# Schematic.net
KiCad netlist of a schematic drawn in EAGLE
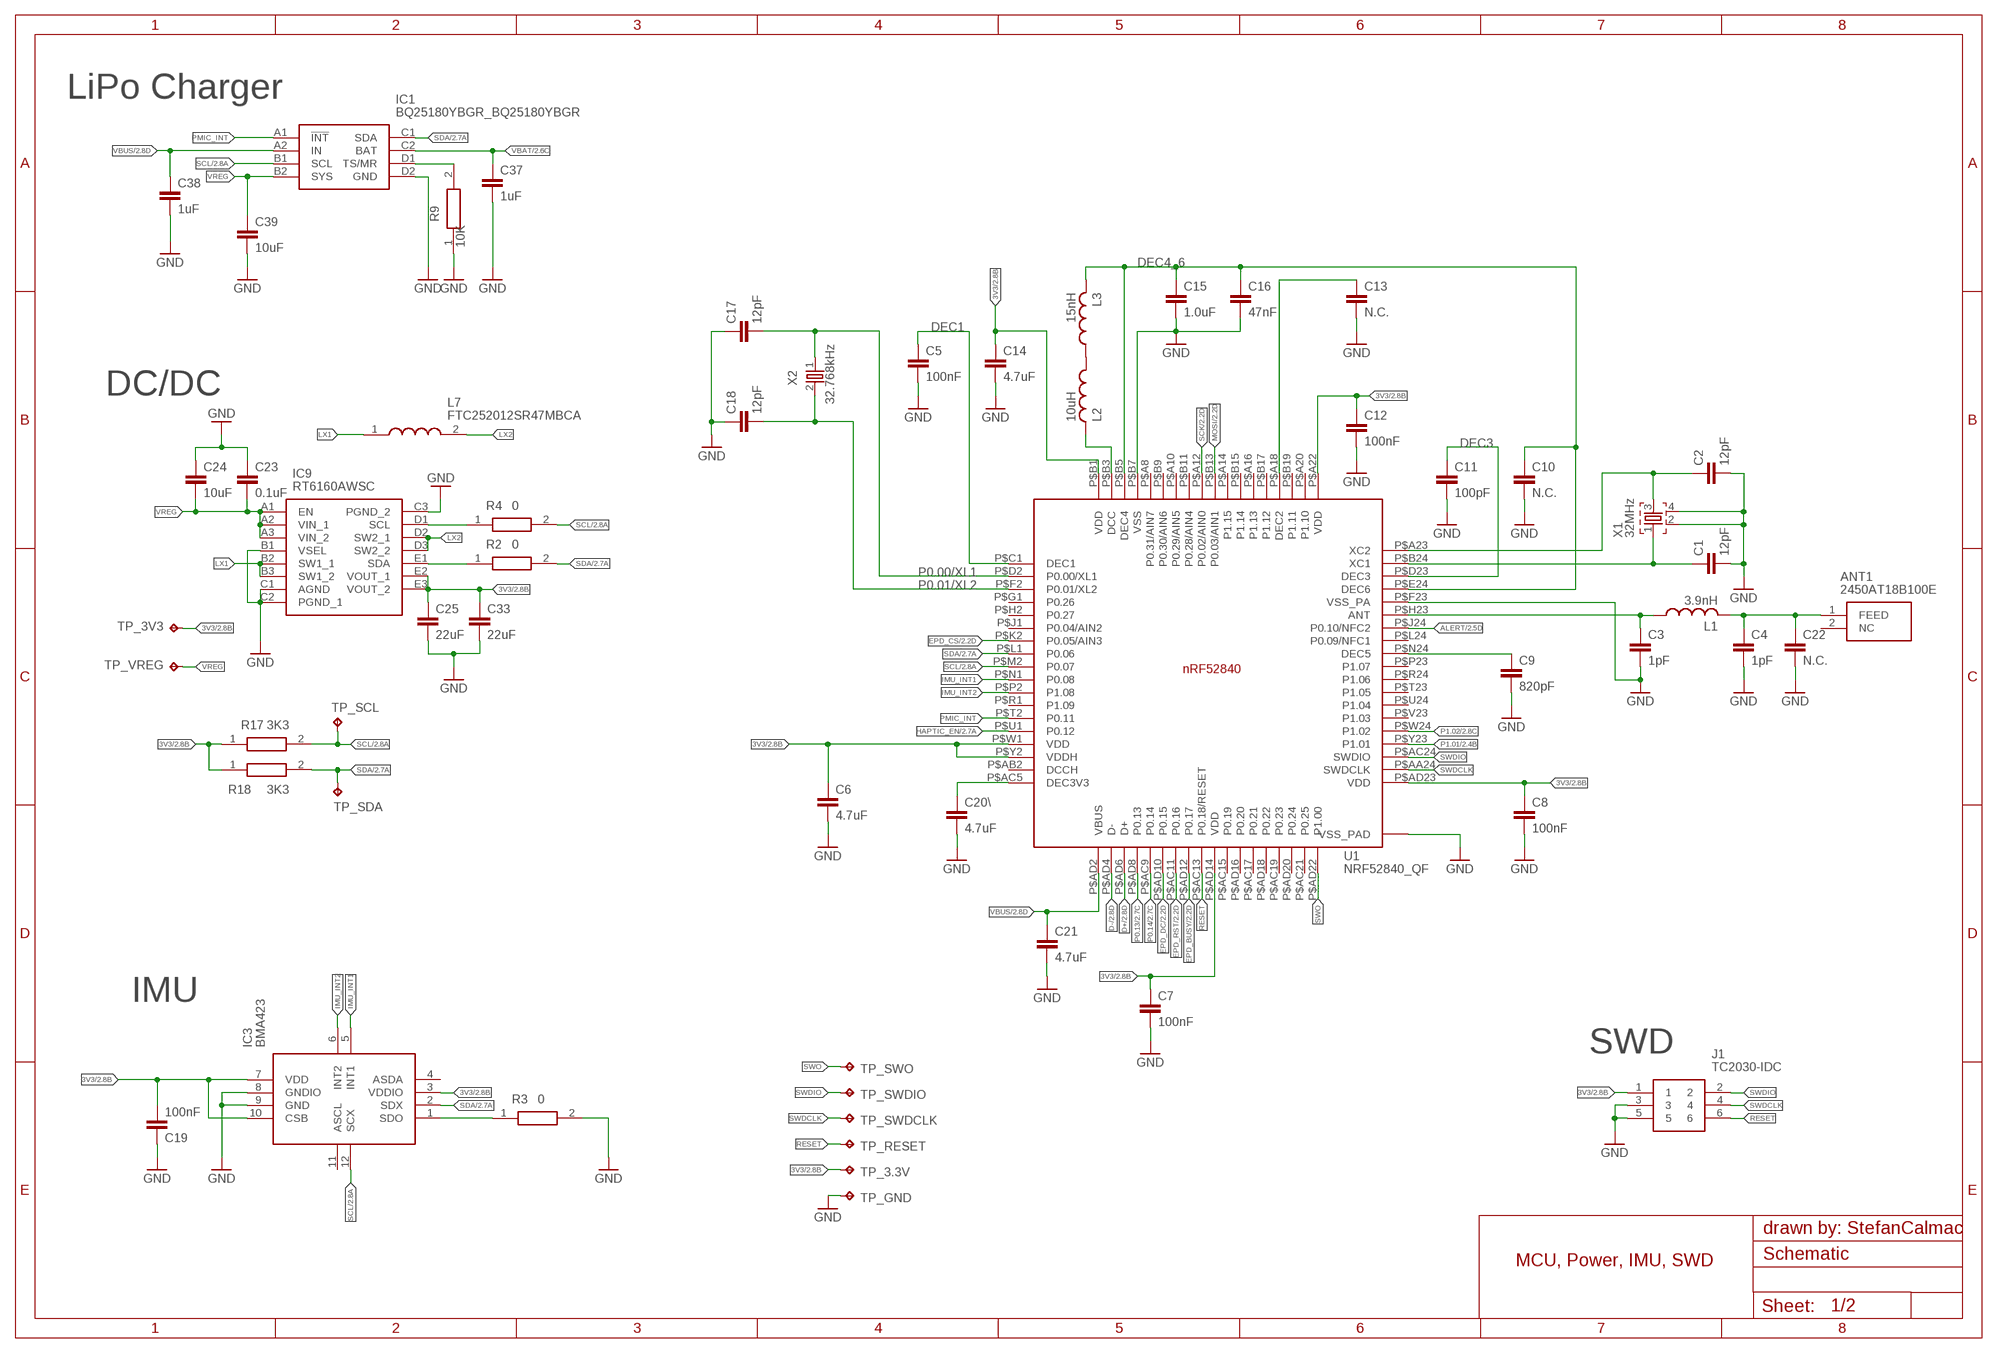
[diagram p0: schematic, sheet 1]
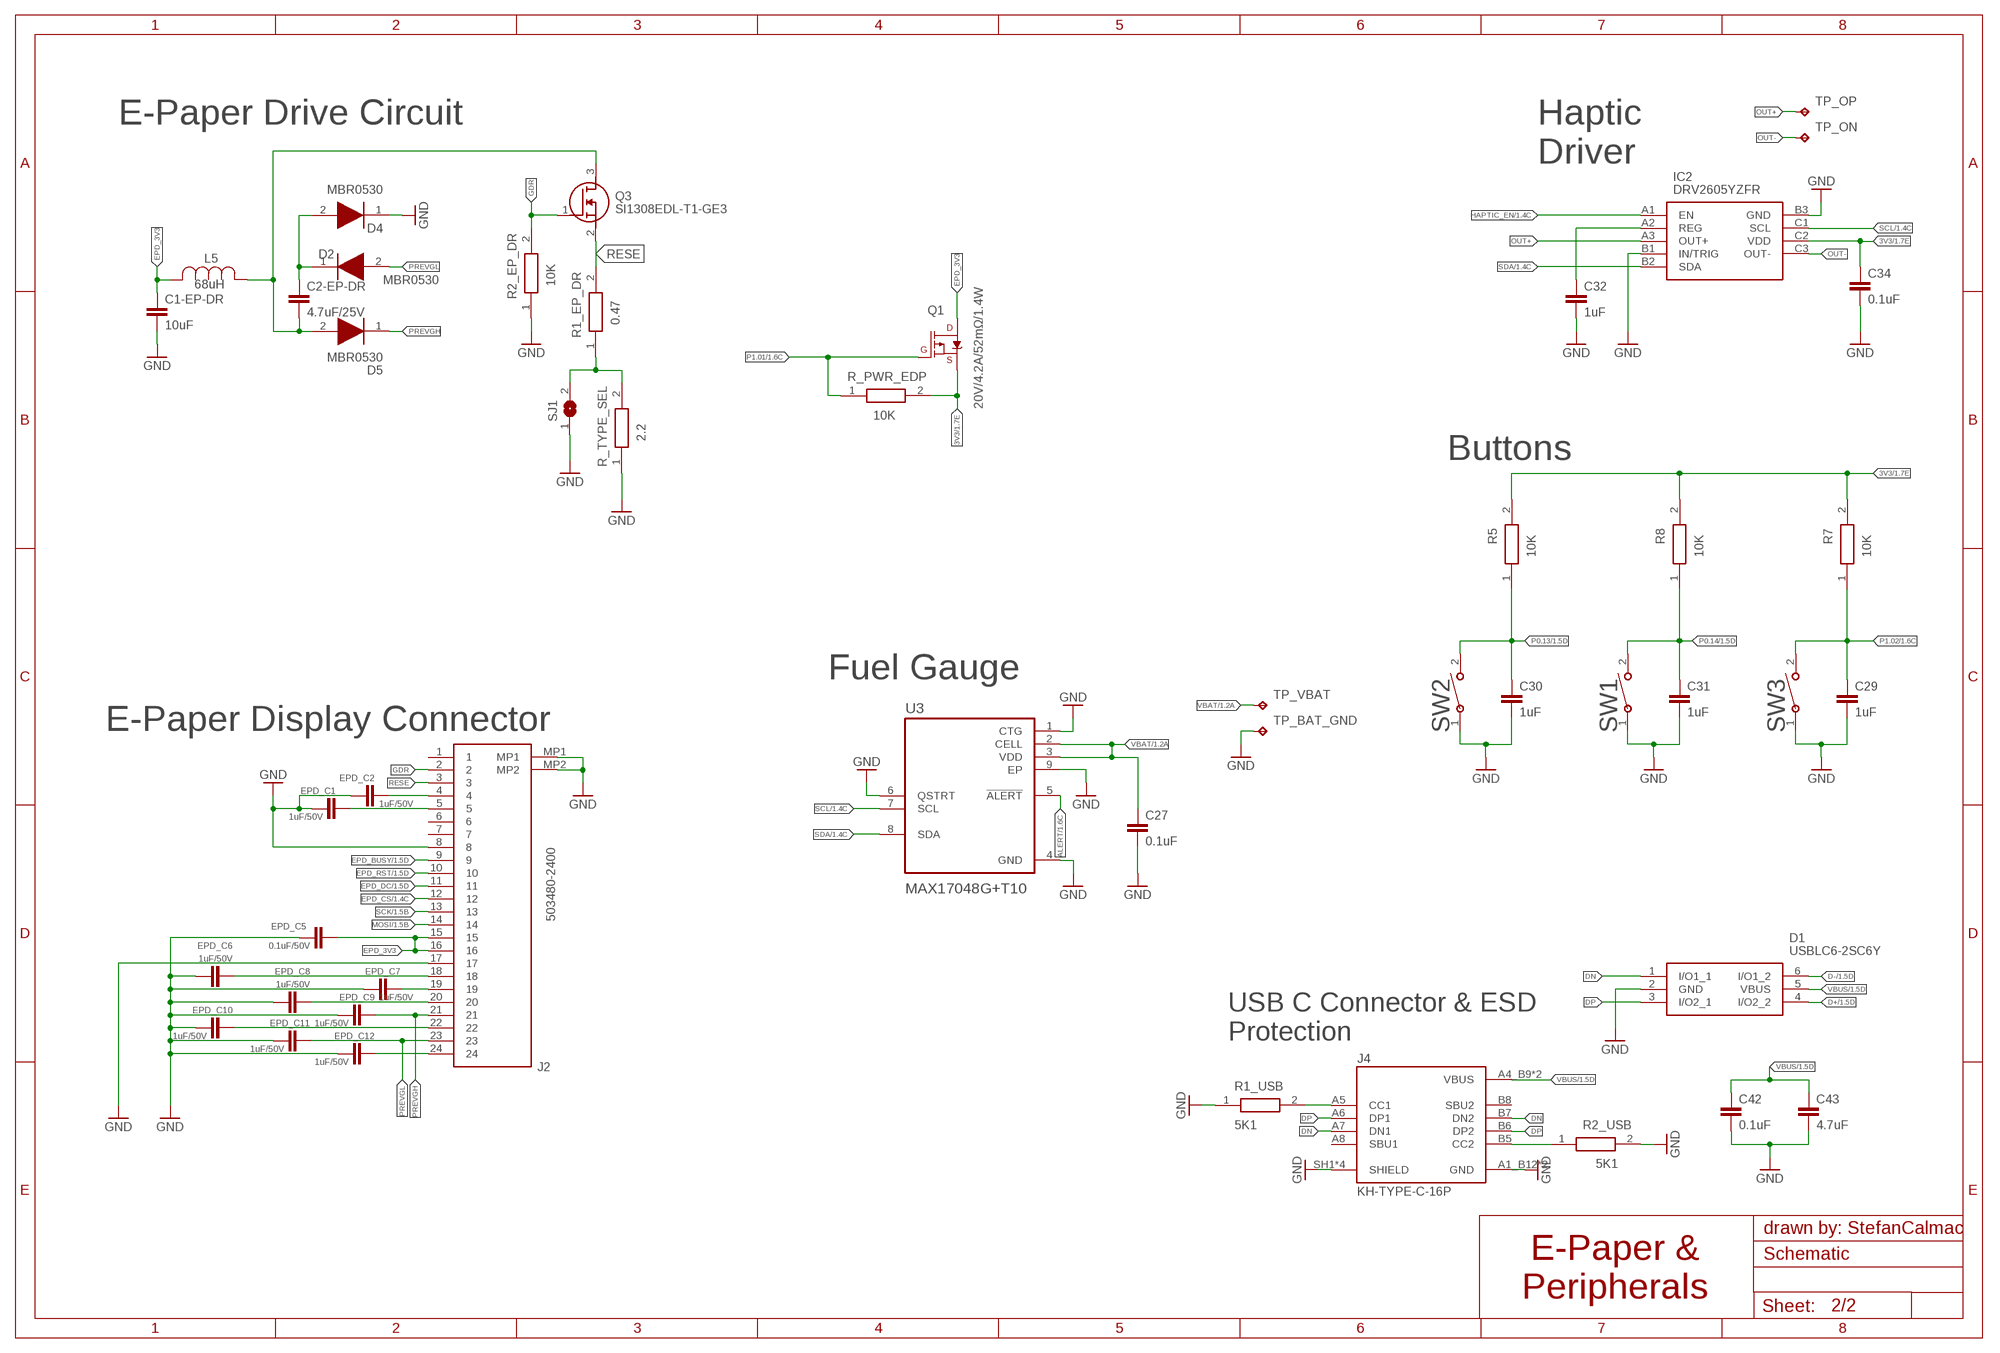
[diagram p1: schematic, sheet 2]

(export (version "E")
  (design (tool "Eeschema 10.0.6"))
  (components
    (comp (ref "ANT1")
      (value "2450AT18B100E")
      (footprint "eagle-import:2450AT18B100E_ANTC3216X140N")
      (fields (field (name "MOUSER_PART_NUMBER") "609-2450AT18B100E"))
      (libsource (lib "eagle-import") (part "2450AT18B100E_2450AT18B100E"))
    )
    (comp (ref "C1")
      (value "12pF")
      (footprint "eagle-import:NORDIC_NRF_3_RESC0201_L")
      (libsource (lib "eagle-import") (part "NORDIC_NRF_3_CAPACITOR_0201_L"))
    )
    (comp (ref "C2")
      (value "12pF")
      (footprint "eagle-import:NORDIC_NRF_3_RESC0201_L")
      (libsource (lib "eagle-import") (part "NORDIC_NRF_3_CAPACITOR_0201_L"))
    )
    (comp (ref "C3")
      (value "1pF")
      (footprint "eagle-import:NORDIC_NRF_3_RESC0201_L")
      (libsource (lib "eagle-import") (part "NORDIC_NRF_3_CAPACITOR_0201_L"))
    )
    (comp (ref "C4")
      (value "1pF")
      (footprint "eagle-import:NORDIC_NRF_3_RESC0201_L")
      (libsource (lib "eagle-import") (part "NORDIC_NRF_3_CAPACITOR_0201_L"))
    )
    (comp (ref "C5")
      (value "100nF")
      (footprint "eagle-import:NORDIC_NRF_3_RESC0201_L")
      (libsource (lib "eagle-import") (part "NORDIC_NRF_3_CAPACITOR_0201_L"))
    )
    (comp (ref "C6")
      (value "4.7uF")
      (footprint "eagle-import:NORDIC_NRF_3_RESC0402_L")
      (libsource (lib "eagle-import") (part "NORDIC_NRF_3_CAPACITOR_0402_L"))
    )
    (comp (ref "C7")
      (value "100nF")
      (footprint "eagle-import:NORDIC_NRF_3_RESC0201_L")
      (libsource (lib "eagle-import") (part "NORDIC_NRF_3_CAPACITOR_0201_L"))
    )
    (comp (ref "C8")
      (value "100nF")
      (footprint "eagle-import:NORDIC_NRF_3_RESC0201_L")
      (libsource (lib "eagle-import") (part "NORDIC_NRF_3_CAPACITOR_0201_L"))
    )
    (comp (ref "C9")
      (value "820pF")
      (footprint "eagle-import:NORDIC_NRF_3_RESC0201_L")
      (libsource (lib "eagle-import") (part "NORDIC_NRF_3_CAPACITOR_0201_L"))
    )
    (comp (ref "C10")
      (value "N.C.")
      (footprint "eagle-import:NORDIC_NRF_3_RESC0201_L")
      (libsource (lib "eagle-import") (part "NORDIC_NRF_3_CAPACITOR_0201_L"))
    )
    (comp (ref "C11")
      (value "100pF")
      (footprint "eagle-import:NORDIC_NRF_3_RESC0201_L")
      (libsource (lib "eagle-import") (part "NORDIC_NRF_3_CAPACITOR_0201_L"))
    )
    (comp (ref "C12")
      (value "100nF")
      (footprint "eagle-import:NORDIC_NRF_3_RESC0201_L")
      (libsource (lib "eagle-import") (part "NORDIC_NRF_3_CAPACITOR_0201_L"))
    )
    (comp (ref "C13")
      (value "N.C.")
      (footprint "eagle-import:NORDIC_NRF_3_RESC0201_L")
      (libsource (lib "eagle-import") (part "NORDIC_NRF_3_CAPACITOR_0201_L"))
    )
    (comp (ref "C14")
      (value "4.7uF")
      (footprint "eagle-import:NORDIC_NRF_3_RESC0402_L")
      (libsource (lib "eagle-import") (part "NORDIC_NRF_3_CAPACITOR_0402_L"))
    )
    (comp (ref "C15")
      (value "1.0uF")
      (footprint "eagle-import:NORDIC_NRF_3_RESC0402_L")
      (libsource (lib "eagle-import") (part "NORDIC_NRF_3_CAPACITOR_0402_L"))
    )
    (comp (ref "C16")
      (value "47nF")
      (footprint "eagle-import:NORDIC_NRF_3_RESC0201_L")
      (libsource (lib "eagle-import") (part "NORDIC_NRF_3_CAPACITOR_0201_L"))
    )
    (comp (ref "C17")
      (value "12pF")
      (footprint "eagle-import:NORDIC_NRF_3_RESC0201_L")
      (libsource (lib "eagle-import") (part "NORDIC_NRF_3_CAPACITOR_0201_L"))
    )
    (comp (ref "C18")
      (value "12pF")
      (footprint "eagle-import:NORDIC_NRF_3_RESC0201_L")
      (libsource (lib "eagle-import") (part "NORDIC_NRF_3_CAPACITOR_0201_L"))
    )
    (comp (ref "C19")
      (value "100nF")
      (footprint "eagle-import:NORDIC_NRF_3_RESC0201_L")
      (libsource (lib "eagle-import") (part "NORDIC_NRF_3_CAPACITOR_0201_L"))
    )
    (comp (ref "C20\\")
      (value "4.7uF")
      (footprint "eagle-import:NORDIC_NRF_3_RESC0402_L")
      (libsource (lib "eagle-import") (part "NORDIC_NRF_3_CAPACITOR_0402_L"))
    )
    (comp (ref "C21")
      (value "4.7uF")
      (footprint "eagle-import:NORDIC_NRF_3_RESC0402_L")
      (libsource (lib "eagle-import") (part "NORDIC_NRF_3_CAPACITOR_0402_L"))
    )
    (comp (ref "C22")
      (value "N.C.")
      (footprint "eagle-import:NORDIC_NRF_3_RESC0201_L")
      (libsource (lib "eagle-import") (part "NORDIC_NRF_3_CAPACITOR_0201_L"))
    )
    (comp (ref "C23")
      (value "0.1uF")
      (footprint "eagle-import:NORDIC_NRF_3_RESC0201_L")
      (libsource (lib "eagle-import") (part "NORDIC_NRF_3_CAPACITOR_0201_L"))
    )
    (comp (ref "C24")
      (value "10uF")
      (footprint "eagle-import:NORDIC_NRF_3_RESC0402_L")
      (libsource (lib "eagle-import") (part "NORDIC_NRF_3_CAPACITOR_0402_L"))
    )
    (comp (ref "C25")
      (value "22uF")
      (footprint "eagle-import:NORDIC_NRF_3_RESC0402_L")
      (libsource (lib "eagle-import") (part "NORDIC_NRF_3_CAPACITOR_0402_L"))
    )
    (comp (ref "C33")
      (value "22uF")
      (footprint "eagle-import:NORDIC_NRF_3_RESC0402_L")
      (libsource (lib "eagle-import") (part "NORDIC_NRF_3_CAPACITOR_0402_L"))
    )
    (comp (ref "C37")
      (value "1uF")
      (footprint "eagle-import:NORDIC_NRF_3_RESC0402_L")
      (libsource (lib "eagle-import") (part "NORDIC_NRF_3_CAPACITOR_0402_L"))
    )
    (comp (ref "C38")
      (value "1uF")
      (footprint "eagle-import:NORDIC_NRF_3_RESC0402_L")
      (libsource (lib "eagle-import") (part "NORDIC_NRF_3_CAPACITOR_0402_L"))
    )
    (comp (ref "C39")
      (value "10uF")
      (footprint "eagle-import:NORDIC_NRF_3_RESC0402_L")
      (libsource (lib "eagle-import") (part "NORDIC_NRF_3_CAPACITOR_0402_L"))
    )
    (comp (ref "IC1")
      (value "BQ25180YBGR_BQ25180YBGR")
      (footprint "eagle-import:BQ25180YBGR_BGA8C40P2X4_100X155X50")
      (fields
        (field (name "ARROW_PART_NUMBER") "BQ25180YBGR")
        (field (name "MOUSER_PART_NUMBER") "595-BQ25180YBGR")
      )
      (libsource (lib "eagle-import") (part "BQ25180YBGR_BQ25180YBGR"))
    )
    (comp (ref "IC3")
      (value "BMA423")
      (footprint "eagle-import:BMA423_BMA423")
      (fields (field (name "MOUSER_PART_NUMBER") "262-BMA423"))
      (libsource (lib "eagle-import") (part "BMA423_BMA423"))
    )
    (comp (ref "IC9")
      (value "RT6160AWSC")
      (footprint "eagle-import:RT6160AWSC_BGA15C40P3X5_140X230X60")
      (fields (field (name "MOUSER_PART_NUMBER") "835-RT6160AWSC"))
      (libsource (lib "eagle-import") (part "RT6160AWSC_RT6160AWSC"))
    )
    (comp (ref "J1")
      (value "TC2030-IDC")
      (footprint "eagle-import:TC2030-IDC_TC2030IDC")
      (libsource (lib "eagle-import") (part "TC2030-IDC_TC2030-IDC"))
    )
    (comp (ref "L1")
      (value "3.9nH")
      (footprint "eagle-import:NORDIC_NRF_2_RESC0402_L")
      (libsource (lib "eagle-import") (part "NORDIC_NRF_2_INDUCTOR_0402_L"))
    )
    (comp (ref "L2")
      (value "10uH")
      (footprint "eagle-import:NORDIC_NRF_2_RESC0603_L")
      (libsource (lib "eagle-import") (part "NORDIC_NRF_2_INDUCTOR_0603_L"))
    )
    (comp (ref "L3")
      (value "15nH")
      (footprint "eagle-import:NORDIC_NRF_2_RESC0402_L")
      (libsource (lib "eagle-import") (part "NORDIC_NRF_2_INDUCTOR_0402_L"))
    )
    (comp (ref "L7")
      (value "FTC252012SR47MBCA")
      (footprint "eagle-import:MLP2016SR47MT0S1_INDC2016X100N")
      (libsource (lib "eagle-import") (part "MLP2016SR47MT0S1_FTC252012SR47MBCA"))
    )
    (comp (ref "R2")
      (value "0")
      (footprint "eagle-import:CPF0201D7K68C1_0201")
      (libsource (lib "eagle-import") (part "CPF0201D7K68C1_CPF0201D7K68C1"))
    )
    (comp (ref "R3")
      (value "0")
      (footprint "eagle-import:CPF0201D7K68C1_0201")
      (libsource (lib "eagle-import") (part "CPF0201D7K68C1_CPF0201D7K68C1"))
    )
    (comp (ref "R4")
      (value "0")
      (footprint "eagle-import:CPF0201D7K68C1_0201")
      (libsource (lib "eagle-import") (part "CPF0201D7K68C1_CPF0201D7K68C1"))
    )
    (comp (ref "R9")
      (value "10K")
      (footprint "eagle-import:CPF0201D7K68C1_0201")
      (libsource (lib "eagle-import") (part "CPF0201D7K68C1_CPF0201D7K68C1"))
    )
    (comp (ref "R17")
      (value "3K3")
      (footprint "eagle-import:CPF0201D7K68C1_0201")
      (libsource (lib "eagle-import") (part "CPF0201D7K68C1_CPF0201D7K68C1"))
    )
    (comp (ref "R18")
      (value "3K3")
      (footprint "eagle-import:CPF0201D7K68C1_0201")
      (libsource (lib "eagle-import") (part "CPF0201D7K68C1_CPF0201D7K68C1"))
    )
    (comp (ref "TP_3.3V")
      (value "HECTOR_WATCH_1_TPTP20R")
      (footprint "eagle-import:HECTOR_WATCH_1_TP20R")
      (libsource (lib "eagle-import") (part "HECTOR_WATCH_1_TPTP20R"))
    )
    (comp (ref "TP_3V3")
      (value "HECTOR_WATCH_1_TPTP20R")
      (footprint "eagle-import:HECTOR_WATCH_1_TP20R")
      (libsource (lib "eagle-import") (part "HECTOR_WATCH_1_TPTP20R"))
    )
    (comp (ref "TP_GND")
      (value "HECTOR_WATCH_1_TPTP20R")
      (footprint "eagle-import:HECTOR_WATCH_1_TP20R")
      (libsource (lib "eagle-import") (part "HECTOR_WATCH_1_TPTP20R"))
    )
    (comp (ref "TP_RESET")
      (value "HECTOR_WATCH_1_TPTP20R")
      (footprint "eagle-import:HECTOR_WATCH_1_TP20R")
      (libsource (lib "eagle-import") (part "HECTOR_WATCH_1_TPTP20R"))
    )
    (comp (ref "TP_SCL")
      (value "HECTOR_WATCH_1_TPTP20R")
      (footprint "eagle-import:HECTOR_WATCH_1_TP20R")
      (libsource (lib "eagle-import") (part "HECTOR_WATCH_1_TPTP20R"))
    )
    (comp (ref "TP_SDA")
      (value "HECTOR_WATCH_1_TPTP20R")
      (footprint "eagle-import:HECTOR_WATCH_1_TP20R")
      (libsource (lib "eagle-import") (part "HECTOR_WATCH_1_TPTP20R"))
    )
    (comp (ref "TP_SWDCLK")
      (value "HECTOR_WATCH_1_TPTP20R")
      (footprint "eagle-import:HECTOR_WATCH_1_TP20R")
      (libsource (lib "eagle-import") (part "HECTOR_WATCH_1_TPTP20R"))
    )
    (comp (ref "TP_SWDIO")
      (value "HECTOR_WATCH_1_TPTP20R")
      (footprint "eagle-import:HECTOR_WATCH_1_TP20R")
      (libsource (lib "eagle-import") (part "HECTOR_WATCH_1_TPTP20R"))
    )
    (comp (ref "TP_SWO")
      (value "HECTOR_WATCH_1_TPTP20R")
      (footprint "eagle-import:HECTOR_WATCH_1_TP20R")
      (libsource (lib "eagle-import") (part "HECTOR_WATCH_1_TPTP20R"))
    )
    (comp (ref "TP_VREG")
      (value "HECTOR_WATCH_1_TPTP20R")
      (footprint "eagle-import:HECTOR_WATCH_1_TP20R")
      (libsource (lib "eagle-import") (part "HECTOR_WATCH_1_TPTP20R"))
    )
    (comp (ref "U1")
      (value "NRF52840_QF")
      (footprint "eagle-import:NORDIC_NRF_4_AQFN50P700X700X85_HS-74N")
      (libsource (lib "eagle-import") (part "NORDIC_NRF_4_NRF52840_QF"))
    )
    (comp (ref "X1")
      (value "32MHz")
      (footprint "eagle-import:NORDIC_NRF_BT-XTAL_2016_N")
      (libsource (lib "eagle-import") (part "NORDIC_NRF_XTAL_32MHZ"))
    )
    (comp (ref "X2")
      (value "32.768kHz")
      (footprint "eagle-import:NORDIC_NRF_1_XTAL_3215_N")
      (libsource (lib "eagle-import") (part "NORDIC_NRF_1_XTAL_32KHZ"))
    )
    (comp (ref "C1-EP-DR")
      (value "10uF")
      (footprint "eagle-import:NORDIC_NRF_3_RESC0402_L")
      (libsource (lib "eagle-import") (part "NORDIC_NRF_3_CAPACITOR_0402_L"))
    )
    (comp (ref "C2-EP-DR")
      (value "4.7uF/25V")
      (footprint "eagle-import:NORDIC_NRF_3_RESC0402_L")
      (libsource (lib "eagle-import") (part "NORDIC_NRF_3_CAPACITOR_0402_L"))
    )
    (comp (ref "C27")
      (value "0.1uF")
      (footprint "eagle-import:NORDIC_NRF_3_RESC0201_L")
      (libsource (lib "eagle-import") (part "NORDIC_NRF_3_CAPACITOR_0201_L"))
    )
    (comp (ref "C29")
      (value "1uF")
      (footprint "eagle-import:NORDIC_NRF_3_RESC0402_L")
      (libsource (lib "eagle-import") (part "NORDIC_NRF_3_CAPACITOR_0402_L"))
    )
    (comp (ref "C30")
      (value "1uF")
      (footprint "eagle-import:NORDIC_NRF_3_RESC0402_L")
      (libsource (lib "eagle-import") (part "NORDIC_NRF_3_CAPACITOR_0402_L"))
    )
    (comp (ref "C31")
      (value "1uF")
      (footprint "eagle-import:NORDIC_NRF_3_RESC0402_L")
      (libsource (lib "eagle-import") (part "NORDIC_NRF_3_CAPACITOR_0402_L"))
    )
    (comp (ref "C32")
      (value "1uF")
      (footprint "eagle-import:NORDIC_NRF_3_RESC0402_L")
      (libsource (lib "eagle-import") (part "NORDIC_NRF_3_CAPACITOR_0402_L"))
    )
    (comp (ref "C34")
      (value "0.1uF")
      (footprint "eagle-import:NORDIC_NRF_3_RESC0201_L")
      (libsource (lib "eagle-import") (part "NORDIC_NRF_3_CAPACITOR_0201_L"))
    )
    (comp (ref "C42")
      (value "0.1uF")
      (footprint "eagle-import:NORDIC_NRF_3_RESC0201_L")
      (libsource (lib "eagle-import") (part "NORDIC_NRF_3_CAPACITOR_0201_L"))
    )
    (comp (ref "C43")
      (value "4.7uF")
      (footprint "eagle-import:NORDIC_NRF_3_RESC0402_L")
      (libsource (lib "eagle-import") (part "NORDIC_NRF_3_CAPACITOR_0402_L"))
    )
    (comp (ref "D1")
      (value "USBLC6-2SC6Y")
      (footprint "eagle-import:SOT95P280X145-6N")
      (fields (field (name "MOUSER_PART_NUMBER") "511-USBLC6-2SC6Y"))
      (libsource (lib "eagle-import") (part "USBLC6-2SC6Y"))
    )
    (comp (ref "D2")
      (value "MBR0530")
      (footprint "eagle-import:ESP32_C6_LIBRARY_5_SOD3716X135N")
      (fields (field (name "MF") "ON Semiconductor"))
      (libsource (lib "eagle-import") (part "ESP32_C6_LIBRARY_5_MBR0530"))
    )
    (comp (ref "D4")
      (value "MBR0530")
      (footprint "eagle-import:ESP32_C6_LIBRARY_5_SOD3716X135N")
      (fields (field (name "MF") "ON Semiconductor"))
      (libsource (lib "eagle-import") (part "ESP32_C6_LIBRARY_5_MBR0530"))
    )
    (comp (ref "D5")
      (value "MBR0530")
      (footprint "eagle-import:ESP32_C6_LIBRARY_5_SOD3716X135N")
      (fields (field (name "MF") "ON Semiconductor"))
      (libsource (lib "eagle-import") (part "ESP32_C6_LIBRARY_5_MBR0530"))
    )
    (comp (ref "EPD_C1")
      (value "1uF/50V")
      (footprint "eagle-import:NORDIC_NRF_3_RESC0402_L")
      (libsource (lib "eagle-import") (part "NORDIC_NRF_3_CAPACITOR_0402_L"))
    )
    (comp (ref "EPD_C2")
      (value "1uF/50V")
      (footprint "eagle-import:NORDIC_NRF_3_RESC0402_L")
      (libsource (lib "eagle-import") (part "NORDIC_NRF_3_CAPACITOR_0402_L"))
    )
    (comp (ref "EPD_C5")
      (value "0.1uF/50V")
      (footprint "eagle-import:NORDIC_NRF_3_RESC0402_L")
      (libsource (lib "eagle-import") (part "NORDIC_NRF_3_CAPACITOR_0402_L"))
    )
    (comp (ref "EPD_C6")
      (value "1uF/50V")
      (footprint "eagle-import:NORDIC_NRF_3_RESC0402_L")
      (libsource (lib "eagle-import") (part "NORDIC_NRF_3_CAPACITOR_0402_L"))
    )
    (comp (ref "EPD_C7")
      (value "1uF/50V")
      (footprint "eagle-import:NORDIC_NRF_3_RESC0402_L")
      (libsource (lib "eagle-import") (part "NORDIC_NRF_3_CAPACITOR_0402_L"))
    )
    (comp (ref "EPD_C8")
      (value "1uF/50V")
      (footprint "eagle-import:NORDIC_NRF_3_RESC0402_L")
      (libsource (lib "eagle-import") (part "NORDIC_NRF_3_CAPACITOR_0402_L"))
    )
    (comp (ref "EPD_C9")
      (value "1uF/50V")
      (footprint "eagle-import:NORDIC_NRF_3_RESC0402_L")
      (libsource (lib "eagle-import") (part "NORDIC_NRF_3_CAPACITOR_0402_L"))
    )
    (comp (ref "EPD_C10")
      (value "1uF/50V")
      (footprint "eagle-import:NORDIC_NRF_3_RESC0402_L")
      (libsource (lib "eagle-import") (part "NORDIC_NRF_3_CAPACITOR_0402_L"))
    )
    (comp (ref "EPD_C11")
      (value "1uF/50V")
      (footprint "eagle-import:NORDIC_NRF_3_RESC0402_L")
      (libsource (lib "eagle-import") (part "NORDIC_NRF_3_CAPACITOR_0402_L"))
    )
    (comp (ref "EPD_C12")
      (value "1uF/50V")
      (footprint "eagle-import:NORDIC_NRF_3_RESC0402_L")
      (libsource (lib "eagle-import") (part "NORDIC_NRF_3_CAPACITOR_0402_L"))
    )
    (comp (ref "IC2")
      (value "DRV2605YZFR")
      (footprint "eagle-import:DRV2605YZFR_BGA9C50P3X3_144X144X62")
      (libsource (lib "eagle-import") (part "DRV2605YZFR_DRV2605YZFR"))
    )
    (comp (ref "J2")
      (value "503480-2400")
      (footprint "eagle-import:503480-2400_5034802400")
      (fields (field (name "MOUSER_PART_NUMBER") "538-503480-2400"))
      (libsource (lib "eagle-import") (part "503480-2400_503480-2400"))
    )
    (comp (ref "J4")
      (value "KH-TYPE-C-16P")
      (footprint "eagle-import:KH-TYPE-C-16P_KINGHELM_KH-TYPE-C-16P")
      (fields (field (name "MF") "kinghelm"))
      (libsource (lib "eagle-import") (part "KH-TYPE-C-16P_KH-TYPE-C-16P"))
    )
    (comp (ref "L5")
      (value "68uH")
      (footprint "eagle-import:ESP32_C6_LIBRARY_2_IND_4828-WE-TPC_WRE")
      (fields
        (field (name "MANUFACTURER_PART_NUMBER") "744043680")
        (field (name "COPYRIGHT") "Copyright (C) 2024 Ultra Librarian. All rights reserved.")
      )
      (libsource (lib "eagle-import") (part "ESP32_C6_LIBRARY_2_744043680IND_4828-WE-TPC_WRE"))
    )
    (comp (ref "Q1")
      (value "20V/4.2A/52mΩ/1.4W")
      (footprint "eagle-import:ESP32_C6_LIBRARY_4_ESP32_C6_LIBRARY_4_ESP32_C6_LIBRARY_4_ESP32_C6_LIBRARY_4_ESP32_WROVER_SPARKFUN-DISCRETESEMI_SOT23-3")
      (libsource (lib "eagle-import") (part "ESP32_C6_LIBRARY_4_ESP32_WROVER_SPARKFUN-DISCRETESEMI_MOSFET_PCH-DMG2305UX-7"))
    )
    (comp (ref "Q3")
      (value "SI1308EDL-T1-GE3")
      (footprint "eagle-import:ESP32_C6_LIBRARY_6_SOT65P210X110-3N")
      (fields (field (name "MF") "Vishay Siliconix"))
      (libsource (lib "eagle-import") (part "ESP32_C6_LIBRARY_6_SI1308EDL-T1-GE3"))
    )
    (comp (ref "R1_EP_DR")
      (value "0.47")
      (footprint "eagle-import:CPF0201D7K68C1_0201")
      (libsource (lib "eagle-import") (part "CPF0201D7K68C1_CPF0201D7K68C1"))
    )
    (comp (ref "R1_USB")
      (value "5K1")
      (footprint "eagle-import:CPF0201D7K68C1_0201")
      (libsource (lib "eagle-import") (part "CPF0201D7K68C1_CPF0201D7K68C1"))
    )
    (comp (ref "R2_EP_DR")
      (value "10K")
      (footprint "eagle-import:CPF0201D7K68C1_0201")
      (libsource (lib "eagle-import") (part "CPF0201D7K68C1_CPF0201D7K68C1"))
    )
    (comp (ref "R2_USB")
      (value "5K1")
      (footprint "eagle-import:CPF0201D7K68C1_0201")
      (libsource (lib "eagle-import") (part "CPF0201D7K68C1_CPF0201D7K68C1"))
    )
    (comp (ref "R5")
      (value "10K")
      (footprint "eagle-import:CPF0201D7K68C1_0201")
      (libsource (lib "eagle-import") (part "CPF0201D7K68C1_CPF0201D7K68C1"))
    )
    (comp (ref "R7")
      (value "10K")
      (footprint "eagle-import:CPF0201D7K68C1_0201")
      (libsource (lib "eagle-import") (part "CPF0201D7K68C1_CPF0201D7K68C1"))
    )
    (comp (ref "R8")
      (value "10K")
      (footprint "eagle-import:CPF0201D7K68C1_0201")
      (libsource (lib "eagle-import") (part "CPF0201D7K68C1_CPF0201D7K68C1"))
    )
    (comp (ref "R_PWR_EDP")
      (value "10K")
      (footprint "eagle-import:CPF0201D7K68C1_0201")
      (libsource (lib "eagle-import") (part "CPF0201D7K68C1_CPF0201D7K68C1"))
    )
    (comp (ref "R_TYPE_SEL")
      (value "2.2")
      (footprint "eagle-import:CPF0201D7K68C1_0201")
      (libsource (lib "eagle-import") (part "CPF0201D7K68C1_CPF0201D7K68C1"))
    )
    (comp (ref "SJ1")
      (value "ESP32_C6_LIBRARY_7_JUMPER_SJ")
      (footprint "eagle-import:ESP32_C6_LIBRARY_7_JUMPER_SJ")
      (libsource (lib "eagle-import") (part "ESP32_C6_LIBRARY_7_JUMPER_SJ"))
    )
    (comp (ref "SW1")
      (value "2025-10-22_07-23-44_LIBRARY_EVP-AKE31ASW_EVP-AKE31A_PAN")
      (footprint "eagle-import:2025-10-22_07-23-44_LIBRARY_SW_EVP-AKE31A_PAN")
      (fields
        (field (name "MANUFACTURER_PART_NUMBER") "EVP-AKE31A")
        (field (name "COPYRIGHT") "Copyright (C) 2025 Ultra Librarian. All rights reserved.")
      )
      (libsource (lib "eagle-import") (part "2025-10-22_07-23-44_LIBRARY_EVP-AKE31ASW_EVP-AKE31A_PAN"))
    )
    (comp (ref "SW2")
      (value "2025-10-22_07-23-44_LIBRARY_EVP-AKE31ASW_EVP-AKE31A_PAN")
      (footprint "eagle-import:2025-10-22_07-23-44_LIBRARY_SW_EVP-AKE31A_PAN")
      (fields
        (field (name "MANUFACTURER_PART_NUMBER") "EVP-AKE31A")
        (field (name "COPYRIGHT") "Copyright (C) 2025 Ultra Librarian. All rights reserved.")
      )
      (libsource (lib "eagle-import") (part "2025-10-22_07-23-44_LIBRARY_EVP-AKE31ASW_EVP-AKE31A_PAN"))
    )
    (comp (ref "SW3")
      (value "2025-10-22_07-23-44_LIBRARY_EVP-AKE31ASW_EVP-AKE31A_PAN")
      (footprint "eagle-import:2025-10-22_07-23-44_LIBRARY_SW_EVP-AKE31A_PAN")
      (fields
        (field (name "MANUFACTURER_PART_NUMBER") "EVP-AKE31A")
        (field (name "COPYRIGHT") "Copyright (C) 2025 Ultra Librarian. All rights reserved.")
      )
      (libsource (lib "eagle-import") (part "2025-10-22_07-23-44_LIBRARY_EVP-AKE31ASW_EVP-AKE31A_PAN"))
    )
    (comp (ref "TP_BAT_GND")
      (value "HECTOR_WATCH_1_TPTP20R")
      (footprint "eagle-import:HECTOR_WATCH_1_TP20R")
      (libsource (lib "eagle-import") (part "HECTOR_WATCH_1_TPTP20R"))
    )
    (comp (ref "TP_ON")
      (value "HECTOR_WATCH_1_TPTP20R")
      (footprint "eagle-import:HECTOR_WATCH_1_TP20R")
      (libsource (lib "eagle-import") (part "HECTOR_WATCH_1_TPTP20R"))
    )
    (comp (ref "TP_OP")
      (value "HECTOR_WATCH_1_TPTP20R")
      (footprint "eagle-import:HECTOR_WATCH_1_TP20R")
      (libsource (lib "eagle-import") (part "HECTOR_WATCH_1_TPTP20R"))
    )
    (comp (ref "TP_VBAT")
      (value "HECTOR_WATCH_1_TPTP20R")
      (footprint "eagle-import:HECTOR_WATCH_1_TP20R")
      (libsource (lib "eagle-import") (part "HECTOR_WATCH_1_TPTP20R"))
    )
    (comp (ref "U3")
      (value "MAX17048G+T10")
      (footprint "eagle-import:ESP32_C6_LIBRARY_SON50P200X200X80-9N")
      (fields (field (name "MF") "Analog Devices"))
      (libsource (lib "eagle-import") (part "ESP32_C6_LIBRARY_MAX17048G+T10"))
    )
  )
  (nets
    (net (code "1") (name "3V3") (class "Default")
      (node (ref "C12") (pin "2") (pinfunction "2_2") (pintype "passive"))
      (node (ref "C14") (pin "1") (pinfunction "1_1") (pintype "passive"))
      (node (ref "C19") (pin "2") (pinfunction "2_2") (pintype "passive"))
      (node (ref "C25") (pin "1") (pinfunction "1_1") (pintype "passive"))
      (node (ref "C33") (pin "1") (pinfunction "1_1") (pintype "passive"))
      (node (ref "C34") (pin "1") (pinfunction "1_1") (pintype "passive"))
      (node (ref "C6") (pin "1") (pinfunction "1_1") (pintype "passive"))
      (node (ref "C7") (pin "2") (pinfunction "2_2") (pintype "passive"))
      (node (ref "C8") (pin "2") (pinfunction "2_2") (pintype "passive"))
      (node (ref "IC2") (pin "C2") (pinfunction "VDD_C2") (pintype "bidirectional"))
      (node (ref "IC3") (pin "10") (pinfunction "CSB_10") (pintype "bidirectional"))
      (node (ref "IC3") (pin "3") (pinfunction "VDDIO_3") (pintype "bidirectional"))
      (node (ref "IC3") (pin "7") (pinfunction "VDD_7") (pintype "bidirectional"))
      (node (ref "IC9") (pin "E2") (pinfunction "VOUT_1_E2") (pintype "bidirectional"))
      (node (ref "IC9") (pin "E3") (pinfunction "VOUT_2_E3") (pintype "bidirectional"))
      (node (ref "J1") (pin "1") (pinfunction "1_1") (pintype "bidirectional"))
      (node (ref "Q1") (pin "2") (pinfunction "S_2") (pintype "bidirectional"))
      (node (ref "R17") (pin "1") (pinfunction "1_1") (pintype "bidirectional"))
      (node (ref "R18") (pin "1") (pinfunction "1_1") (pintype "bidirectional"))
      (node (ref "R5") (pin "2") (pinfunction "2_2") (pintype "bidirectional"))
      (node (ref "R7") (pin "2") (pinfunction "2_2") (pintype "bidirectional"))
      (node (ref "R8") (pin "2") (pinfunction "2_2") (pintype "bidirectional"))
      (node (ref "R_PWR_EDP") (pin "2") (pinfunction "2_2") (pintype "bidirectional"))
      (node (ref "TP_3.3V") (pin "TP") (pinfunction "TP_TP") (pintype "input"))
      (node (ref "TP_3V3") (pin "TP") (pinfunction "TP_TP") (pintype "input"))
      (node (ref "U1") (pin "P$A22") (pinfunction "VDD_P$A22") (pintype "power_in"))
      (node (ref "U1") (pin "P$AD14") (pinfunction "VDD_P$AD14") (pintype "power_in"))
      (node (ref "U1") (pin "P$AD23") (pinfunction "VDD_P$AD23") (pintype "power_in"))
      (node (ref "U1") (pin "P$B1") (pinfunction "VDD_P$B1") (pintype "power_in"))
      (node (ref "U1") (pin "P$W1") (pinfunction "VDD_P$W1") (pintype "power_in"))
      (node (ref "U1") (pin "P$Y2") (pinfunction "VDDH_P$Y2") (pintype "power_in"))
    )
    (net (code "2") (name "ALERT") (class "Default")
      (node (ref "U1") (pin "P$J24") (pinfunction "P0.10/NFC2_P$J24") (pintype "bidirectional"))
      (node (ref "U3") (pin "5") (pinfunction "~{ALERT}_5") (pintype "output"))
    )
    (net (code "3") (name "D+") (class "Default")
      (node (ref "D1") (pin "4") (pinfunction "I/O2_2_4") (pintype "bidirectional"))
      (node (ref "U1") (pin "P$AD6") (pinfunction "D+_P$AD6") (pintype "bidirectional"))
    )
    (net (code "4") (name "D-") (class "Default")
      (node (ref "D1") (pin "6") (pinfunction "I/O1_2_6") (pintype "bidirectional"))
      (node (ref "U1") (pin "P$AD4") (pinfunction "D-_P$AD4") (pintype "bidirectional"))
    )
    (net (code "5") (name "DEC1") (class "Default")
      (node (ref "C5") (pin "2") (pinfunction "2_2") (pintype "passive"))
      (node (ref "U1") (pin "P$C1") (pinfunction "DEC1_P$C1") (pintype "power_in"))
    )
    (net (code "6") (name "DEC3") (class "Default")
      (node (ref "C11") (pin "2") (pinfunction "2_2") (pintype "passive"))
      (node (ref "U1") (pin "P$D23") (pinfunction "DEC3_P$D23") (pintype "bidirectional"))
    )
    (net (code "7") (name "DEC4_6") (class "Default")
      (node (ref "C10") (pin "2") (pinfunction "2_2") (pintype "passive"))
      (node (ref "C15") (pin "1") (pinfunction "1_1") (pintype "passive"))
      (node (ref "C16") (pin "2") (pinfunction "2_2") (pintype "passive"))
      (node (ref "L3") (pin "2") (pinfunction "2_2") (pintype "passive"))
      (node (ref "U1") (pin "P$B5") (pinfunction "DEC4_P$B5") (pintype "power_in"))
      (node (ref "U1") (pin "P$E24") (pinfunction "DEC6_P$E24") (pintype "bidirectional"))
    )
    (net (code "8") (name "DN") (class "Default")
      (node (ref "D1") (pin "1") (pinfunction "I/O1_1_1") (pintype "bidirectional"))
      (node (ref "J4") (pin "A7") (pinfunction "DN1_A7") (pintype "bidirectional"))
      (node (ref "J4") (pin "B7") (pinfunction "DN2_B7") (pintype "bidirectional"))
    )
    (net (code "9") (name "DP") (class "Default")
      (node (ref "D1") (pin "3") (pinfunction "I/O2_1_3") (pintype "bidirectional"))
      (node (ref "J4") (pin "A6") (pinfunction "DP1_A6") (pintype "bidirectional"))
      (node (ref "J4") (pin "B6") (pinfunction "DP2_B6") (pintype "bidirectional"))
    )
    (net (code "10") (name "EPD_3V3") (class "Default")
      (node (ref "C1-EP-DR") (pin "1") (pinfunction "1_1") (pintype "passive"))
      (node (ref "EPD_C5") (pin "2") (pinfunction "2_2") (pintype "passive"))
      (node (ref "J2") (pin "15") (pinfunction "15_15") (pintype "bidirectional"))
      (node (ref "J2") (pin "16") (pinfunction "16_16") (pintype "bidirectional"))
      (node (ref "L5") (pin "2") (pinfunction "2_2") (pintype "passive"))
      (node (ref "Q1") (pin "3") (pinfunction "D_3") (pintype "bidirectional"))
    )
    (net (code "11") (name "EPD_BUSY") (class "Default")
      (node (ref "J2") (pin "9") (pinfunction "9_9") (pintype "bidirectional"))
      (node (ref "U1") (pin "P$AD12") (pinfunction "P0.17_P$AD12") (pintype "bidirectional"))
    )
    (net (code "12") (name "EPD_CS") (class "Default")
      (node (ref "J2") (pin "12") (pinfunction "12_12") (pintype "bidirectional"))
      (node (ref "U1") (pin "P$K2") (pinfunction "P0.05/AIN3_P$K2") (pintype "bidirectional"))
    )
    (net (code "13") (name "EPD_DC") (class "Default")
      (node (ref "J2") (pin "11") (pinfunction "11_11") (pintype "bidirectional"))
      (node (ref "U1") (pin "P$AD10") (pinfunction "P0.15_P$AD10") (pintype "bidirectional"))
    )
    (net (code "14") (name "EPD_RST") (class "Default")
      (node (ref "J2") (pin "10") (pinfunction "10_10") (pintype "bidirectional"))
      (node (ref "U1") (pin "P$AC11") (pinfunction "P0.16_P$AC11") (pintype "bidirectional"))
    )
    (net (code "15") (name "GDR") (class "Default")
      (node (ref "J2") (pin "2") (pinfunction "2_2") (pintype "bidirectional"))
      (node (ref "Q3") (pin "1") (pinfunction "G_1") (pintype "bidirectional"))
      (node (ref "R2_EP_DR") (pin "2") (pinfunction "2_2") (pintype "bidirectional"))
    )
    (net (code "16") (name "GND") (class "Default")
      (node (ref "C1") (pin "1") (pinfunction "1_1") (pintype "passive"))
      (node (ref "C1-EP-DR") (pin "2") (pinfunction "2_2") (pintype "passive"))
      (node (ref "C10") (pin "1") (pinfunction "1_1") (pintype "passive"))
      (node (ref "C11") (pin "1") (pinfunction "1_1") (pintype "passive"))
      (node (ref "C12") (pin "1") (pinfunction "1_1") (pintype "passive"))
      (node (ref "C13") (pin "1") (pinfunction "1_1") (pintype "passive"))
      (node (ref "C14") (pin "2") (pinfunction "2_2") (pintype "passive"))
      (node (ref "C15") (pin "2") (pinfunction "2_2") (pintype "passive"))
      (node (ref "C16") (pin "1") (pinfunction "1_1") (pintype "passive"))
      (node (ref "C17") (pin "1") (pinfunction "1_1") (pintype "passive"))
      (node (ref "C18") (pin "1") (pinfunction "1_1") (pintype "passive"))
      (node (ref "C19") (pin "1") (pinfunction "1_1") (pintype "passive"))
      (node (ref "C2") (pin "2") (pinfunction "2_2") (pintype "passive"))
      (node (ref "C20\\") (pin "2") (pinfunction "2_2") (pintype "passive"))
      (node (ref "C21") (pin "2") (pinfunction "2_2") (pintype "passive"))
      (node (ref "C22") (pin "1") (pinfunction "1_1") (pintype "passive"))
      (node (ref "C23") (pin "1") (pinfunction "1_1") (pintype "passive"))
      (node (ref "C24") (pin "1") (pinfunction "1_1") (pintype "passive"))
      (node (ref "C25") (pin "2") (pinfunction "2_2") (pintype "passive"))
      (node (ref "C27") (pin "2") (pinfunction "2_2") (pintype "passive"))
      (node (ref "C29") (pin "2") (pinfunction "2_2") (pintype "passive"))
      (node (ref "C3") (pin "1") (pinfunction "1_1") (pintype "passive"))
      (node (ref "C30") (pin "2") (pinfunction "2_2") (pintype "passive"))
      (node (ref "C31") (pin "2") (pinfunction "2_2") (pintype "passive"))
      (node (ref "C32") (pin "2") (pinfunction "2_2") (pintype "passive"))
      (node (ref "C33") (pin "2") (pinfunction "2_2") (pintype "passive"))
      (node (ref "C34") (pin "2") (pinfunction "2_2") (pintype "passive"))
      (node (ref "C37") (pin "2") (pinfunction "2_2") (pintype "passive"))
      (node (ref "C38") (pin "2") (pinfunction "2_2") (pintype "passive"))
      (node (ref "C39") (pin "2") (pinfunction "2_2") (pintype "passive"))
      (node (ref "C4") (pin "1") (pinfunction "1_1") (pintype "passive"))
      (node (ref "C42") (pin "2") (pinfunction "2_2") (pintype "passive"))
      (node (ref "C43") (pin "2") (pinfunction "2_2") (pintype "passive"))
      (node (ref "C5") (pin "1") (pinfunction "1_1") (pintype "passive"))
      (node (ref "C6") (pin "2") (pinfunction "2_2") (pintype "passive"))
      (node (ref "C7") (pin "1") (pinfunction "1_1") (pintype "passive"))
      (node (ref "C8") (pin "1") (pinfunction "1_1") (pintype "passive"))
      (node (ref "C9") (pin "1") (pinfunction "1_1") (pintype "passive"))
      (node (ref "D1") (pin "2") (pinfunction "GND_2") (pintype "bidirectional"))
      (node (ref "D4") (pin "1") (pinfunction "K_1") (pintype "bidirectional"))
      (node (ref "EPD_C1") (pin "1") (pinfunction "1_1") (pintype "passive"))
      (node (ref "EPD_C10") (pin "1") (pinfunction "1_1") (pintype "passive"))
      (node (ref "EPD_C11") (pin "1") (pinfunction "1_1") (pintype "passive"))
      (node (ref "EPD_C12") (pin "1") (pinfunction "1_1") (pintype "passive"))
      (node (ref "EPD_C2") (pin "1") (pinfunction "1_1") (pintype "passive"))
      (node (ref "EPD_C5") (pin "1") (pinfunction "1_1") (pintype "passive"))
      (node (ref "EPD_C6") (pin "1") (pinfunction "1_1") (pintype "passive"))
      (node (ref "EPD_C7") (pin "1") (pinfunction "1_1") (pintype "passive"))
      (node (ref "EPD_C8") (pin "1") (pinfunction "1_1") (pintype "passive"))
      (node (ref "EPD_C9") (pin "1") (pinfunction "1_1") (pintype "passive"))
      (node (ref "IC1") (pin "D2") (pinfunction "GND_D2") (pintype "bidirectional"))
      (node (ref "IC2") (pin "B1") (pinfunction "IN/TRIG_B1") (pintype "bidirectional"))
      (node (ref "IC2") (pin "B3") (pinfunction "GND_B3") (pintype "bidirectional"))
      (node (ref "IC3") (pin "8") (pinfunction "GNDIO_8") (pintype "bidirectional"))
      (node (ref "IC3") (pin "9") (pinfunction "GND_9") (pintype "bidirectional"))
      (node (ref "IC9") (pin "B1") (pinfunction "VSEL_B1") (pintype "bidirectional"))
      (node (ref "IC9") (pin "C1") (pinfunction "AGND_C1") (pintype "bidirectional"))
      (node (ref "IC9") (pin "C2") (pinfunction "PGND_1_C2") (pintype "bidirectional"))
      (node (ref "IC9") (pin "C3") (pinfunction "PGND_2_C3") (pintype "bidirectional"))
      (node (ref "J1") (pin "3") (pinfunction "3_3") (pintype "bidirectional"))
      (node (ref "J1") (pin "5") (pinfunction "5_5") (pintype "bidirectional"))
      (node (ref "J2") (pin "17") (pinfunction "17_17") (pintype "bidirectional"))
      (node (ref "J2") (pin "8") (pinfunction "8_8") (pintype "bidirectional"))
      (node (ref "J2") (pin "MP1") (pinfunction "MP1_MP1") (pintype "bidirectional"))
      (node (ref "J2") (pin "MP2") (pinfunction "MP2_MP2") (pintype "bidirectional"))
      (node (ref "J4") (pin "A12_B1") (pinfunction "GND_A12_B1") (pintype "power_in"))
      (node (ref "J4") (pin "A1_B12") (pinfunction "GND_A1_B12") (pintype "power_in"))
      (node (ref "J4") (pin "SH1") (pinfunction "SHIELD_SH1") (pintype "passive"))
      (node (ref "J4") (pin "SH2") (pinfunction "SHIELD_SH2") (pintype "passive"))
      (node (ref "J4") (pin "SH3") (pinfunction "SHIELD_SH3") (pintype "passive"))
      (node (ref "J4") (pin "SH4") (pinfunction "SHIELD_SH4") (pintype "passive"))
      (node (ref "R1_USB") (pin "1") (pinfunction "1_1") (pintype "bidirectional"))
      (node (ref "R2_EP_DR") (pin "1") (pinfunction "1_1") (pintype "bidirectional"))
      (node (ref "R2_USB") (pin "2") (pinfunction "2_2") (pintype "bidirectional"))
      (node (ref "R3") (pin "2") (pinfunction "2_2") (pintype "bidirectional"))
      (node (ref "R9") (pin "1") (pinfunction "1_1") (pintype "bidirectional"))
      (node (ref "R_TYPE_SEL") (pin "1") (pinfunction "1_1") (pintype "bidirectional"))
      (node (ref "SJ1") (pin "1") (pinfunction "1_1") (pintype "passive"))
      (node (ref "SW1") (pin "1") (pinfunction "1_1") (pintype "passive"))
      (node (ref "SW2") (pin "1") (pinfunction "1_1") (pintype "passive"))
      (node (ref "SW3") (pin "1") (pinfunction "1_1") (pintype "passive"))
      (node (ref "TP_BAT_GND") (pin "TP") (pinfunction "TP_TP") (pintype "input"))
      (node (ref "TP_GND") (pin "TP") (pinfunction "TP_TP") (pintype "input"))
      (node (ref "U1") (pin "P$74") (pinfunction "VSS_PAD_P$74") (pintype "bidirectional"))
      (node (ref "U1") (pin "P$75") (pinfunction "VSS_PAD_P$75") (pintype "bidirectional"))
      (node (ref "U1") (pin "P$76") (pinfunction "VSS_PAD_P$76") (pintype "bidirectional"))
      (node (ref "U1") (pin "P$77") (pinfunction "VSS_PAD_P$77") (pintype "bidirectional"))
      (node (ref "U1") (pin "P$78") (pinfunction "VSS_PAD_P$78") (pintype "bidirectional"))
      (node (ref "U1") (pin "P$79") (pinfunction "VSS_PAD_P$79") (pintype "bidirectional"))
      (node (ref "U1") (pin "P$80") (pinfunction "VSS_PAD_P$80") (pintype "bidirectional"))
      (node (ref "U1") (pin "P$81") (pinfunction "VSS_PAD_P$81") (pintype "bidirectional"))
      (node (ref "U1") (pin "P$82") (pinfunction "VSS_PAD_P$82") (pintype "bidirectional"))
      (node (ref "U1") (pin "P$83") (pinfunction "VSS_PAD_P$83") (pintype "bidirectional"))
      (node (ref "U1") (pin "P$84") (pinfunction "VSS_PAD_P$84") (pintype "bidirectional"))
      (node (ref "U1") (pin "P$85") (pinfunction "VSS_PAD_P$85") (pintype "bidirectional"))
      (node (ref "U1") (pin "P$86") (pinfunction "VSS_PAD_P$86") (pintype "bidirectional"))
      (node (ref "U1") (pin "P$87") (pinfunction "VSS_PAD_P$87") (pintype "bidirectional"))
      (node (ref "U1") (pin "P$88") (pinfunction "VSS_PAD_P$88") (pintype "bidirectional"))
      (node (ref "U1") (pin "P$89") (pinfunction "VSS_PAD_P$89") (pintype "bidirectional"))
      (node (ref "U1") (pin "P$90") (pinfunction "VSS_PAD_P$90") (pintype "bidirectional"))
      (node (ref "U1") (pin "P$B7") (pinfunction "VSS_P$B7") (pintype "power_in"))
      (node (ref "U1") (pin "P$F23") (pinfunction "VSS_PA_P$F23") (pintype "bidirectional"))
      (node (ref "U3") (pin "1") (pinfunction "CTG_1") (pintype "power_in"))
      (node (ref "U3") (pin "4") (pinfunction "GND_4") (pintype "power_in"))
      (node (ref "U3") (pin "6") (pinfunction "QSTRT_6") (pintype "input"))
      (node (ref "U3") (pin "9") (pinfunction "EP_9") (pintype "power_in"))
      (node (ref "X1") (pin "2") (pinfunction "2_2") (pintype "passive"))
      (node (ref "X1") (pin "4") (pinfunction "4_4") (pintype "passive"))
    )
    (net (code "17") (name "HAPTIC_EN") (class "Default")
      (node (ref "IC2") (pin "A1") (pinfunction "EN_A1") (pintype "bidirectional"))
      (node (ref "U1") (pin "P$U1") (pinfunction "P0.12_P$U1") (pintype "bidirectional"))
    )
    (net (code "18") (name "IMU_INT1") (class "Default")
      (node (ref "IC3") (pin "5") (pinfunction "INT1_5") (pintype "bidirectional"))
      (node (ref "U1") (pin "P$N1") (pinfunction "P0.08_P$N1") (pintype "bidirectional"))
    )
    (net (code "19") (name "IMU_INT2") (class "Default")
      (node (ref "IC3") (pin "6") (pinfunction "INT2_6") (pintype "bidirectional"))
      (node (ref "U1") (pin "P$P2") (pinfunction "P1.08_P$P2") (pintype "bidirectional"))
    )
    (net (code "20") (name "LX1") (class "Default")
      (node (ref "IC9") (pin "B2") (pinfunction "SW1_1_B2") (pintype "bidirectional"))
      (node (ref "IC9") (pin "B3") (pinfunction "SW1_2_B3") (pintype "bidirectional"))
      (node (ref "L7") (pin "1") (pinfunction "1_1") (pintype "bidirectional"))
    )
    (net (code "21") (name "LX2") (class "Default")
      (node (ref "IC9") (pin "D2") (pinfunction "SW2_1_D2") (pintype "bidirectional"))
      (node (ref "IC9") (pin "D3") (pinfunction "SW2_2_D3") (pintype "bidirectional"))
      (node (ref "L7") (pin "2") (pinfunction "2_2") (pintype "bidirectional"))
    )
    (net (code "22") (name "MOSI") (class "Default")
      (node (ref "J2") (pin "14") (pinfunction "14_14") (pintype "bidirectional"))
      (node (ref "U1") (pin "P$B13") (pinfunction "P0.03/AIN1_P$B13") (pintype "bidirectional"))
    )
    (net (code "23") (name "Net-(ANT1-FEED)") (class "Default")
      (node (ref "ANT1") (pin "1") (pinfunction "FEED_1") (pintype "input"))
      (node (ref "C22") (pin "2") (pinfunction "2_2") (pintype "passive"))
      (node (ref "C4") (pin "2") (pinfunction "2_2") (pintype "passive"))
      (node (ref "L1") (pin "2") (pinfunction "2_2") (pintype "passive"))
    )
    (net (code "24") (name "Net-(D2-K)") (class "Default")
      (node (ref "C2-EP-DR") (pin "1") (pinfunction "1_1") (pintype "passive"))
      (node (ref "D2") (pin "1") (pinfunction "K_1") (pintype "bidirectional"))
      (node (ref "D4") (pin "2") (pinfunction "A_2") (pintype "bidirectional"))
    )
    (net (code "25") (name "Net-(D5-A)") (class "Default")
      (node (ref "C2-EP-DR") (pin "2") (pinfunction "2_2") (pintype "passive"))
      (node (ref "D5") (pin "2") (pinfunction "A_2") (pintype "bidirectional"))
      (node (ref "L5") (pin "1") (pinfunction "1_1") (pintype "passive"))
      (node (ref "Q3") (pin "3") (pinfunction "D_3") (pintype "bidirectional"))
    )
    (net (code "26") (name "Net-(EPD_C1-Pad2)") (class "Default")
      (node (ref "EPD_C1") (pin "2") (pinfunction "2_2") (pintype "passive"))
      (node (ref "J2") (pin "5") (pinfunction "5_5") (pintype "bidirectional"))
    )
    (net (code "27") (name "Net-(EPD_C2-Pad2)") (class "Default")
      (node (ref "EPD_C2") (pin "2") (pinfunction "2_2") (pintype "passive"))
      (node (ref "J2") (pin "4") (pinfunction "4_4") (pintype "bidirectional"))
    )
    (net (code "28") (name "Net-(EPD_C6-Pad2)") (class "Default")
      (node (ref "EPD_C6") (pin "2") (pinfunction "2_2") (pintype "passive"))
      (node (ref "J2") (pin "18") (pinfunction "18_18") (pintype "bidirectional"))
    )
    (net (code "29") (name "Net-(EPD_C7-Pad2)") (class "Default")
      (node (ref "EPD_C7") (pin "2") (pinfunction "2_2") (pintype "passive"))
      (node (ref "J2") (pin "19") (pinfunction "19_19") (pintype "bidirectional"))
    )
    (net (code "30") (name "Net-(EPD_C8-Pad2)") (class "Default")
      (node (ref "EPD_C8") (pin "2") (pinfunction "2_2") (pintype "passive"))
      (node (ref "J2") (pin "20") (pinfunction "20_20") (pintype "bidirectional"))
    )
    (net (code "31") (name "Net-(EPD_C10-Pad2)") (class "Default")
      (node (ref "EPD_C10") (pin "2") (pinfunction "2_2") (pintype "passive"))
      (node (ref "J2") (pin "22") (pinfunction "22_22") (pintype "bidirectional"))
    )
    (net (code "32") (name "Net-(EPD_C12-Pad2)") (class "Default")
      (node (ref "EPD_C12") (pin "2") (pinfunction "2_2") (pintype "passive"))
      (node (ref "J2") (pin "24") (pinfunction "24_24") (pintype "bidirectional"))
    )
    (net (code "33") (name "Net-(IC1-TS{slash}MR)") (class "Default")
      (node (ref "IC1") (pin "D1") (pinfunction "TS/MR_D1") (pintype "bidirectional"))
      (node (ref "R9") (pin "2") (pinfunction "2_2") (pintype "bidirectional"))
    )
    (net (code "34") (name "Net-(IC2-REG)") (class "Default")
      (node (ref "C32") (pin "1") (pinfunction "1_1") (pintype "passive"))
      (node (ref "IC2") (pin "A2") (pinfunction "REG_A2") (pintype "bidirectional"))
    )
    (net (code "35") (name "Net-(IC3-SDO)") (class "Default")
      (node (ref "IC3") (pin "1") (pinfunction "SDO_1") (pintype "bidirectional"))
      (node (ref "R3") (pin "1") (pinfunction "1_1") (pintype "bidirectional"))
    )
    (net (code "36") (name "Net-(IC9-SCL)") (class "Default")
      (node (ref "IC9") (pin "D1") (pinfunction "SCL_D1") (pintype "bidirectional"))
      (node (ref "R4") (pin "1") (pinfunction "1_1") (pintype "bidirectional"))
    )
    (net (code "37") (name "Net-(IC9-SDA)") (class "Default")
      (node (ref "IC9") (pin "E1") (pinfunction "SDA_E1") (pintype "bidirectional"))
      (node (ref "R2") (pin "1") (pinfunction "1_1") (pintype "bidirectional"))
    )
    (net (code "38") (name "Net-(J4-CC1)") (class "Default")
      (node (ref "J4") (pin "A5") (pinfunction "CC1_A5") (pintype "bidirectional"))
      (node (ref "R1_USB") (pin "2") (pinfunction "2_2") (pintype "bidirectional"))
    )
    (net (code "39") (name "Net-(J4-CC2)") (class "Default")
      (node (ref "J4") (pin "B5") (pinfunction "CC2_B5") (pintype "bidirectional"))
      (node (ref "R2_USB") (pin "1") (pinfunction "1_1") (pintype "bidirectional"))
    )
    (net (code "40") (name "Net-(L2-Pad1)") (class "Default")
      (node (ref "L2") (pin "1") (pinfunction "1_1") (pintype "passive"))
      (node (ref "L3") (pin "1") (pinfunction "1_1") (pintype "passive"))
    )
    (net (code "41") (name "Net-(R1_EP_DR-Pad1)") (class "Default")
      (node (ref "R1_EP_DR") (pin "1") (pinfunction "1_1") (pintype "bidirectional"))
      (node (ref "R_TYPE_SEL") (pin "2") (pinfunction "2_2") (pintype "bidirectional"))
      (node (ref "SJ1") (pin "2") (pinfunction "2_2") (pintype "passive"))
    )
    (net (code "42") (name "Net-(U1-ANT)") (class "Default")
      (node (ref "C3") (pin "2") (pinfunction "2_2") (pintype "passive"))
      (node (ref "L1") (pin "1") (pinfunction "1_1") (pintype "passive"))
      (node (ref "U1") (pin "P$H23") (pinfunction "ANT_P$H23") (pintype "bidirectional"))
    )
    (net (code "43") (name "Net-(U1-DCC)") (class "Default")
      (node (ref "L2") (pin "2") (pinfunction "2_2") (pintype "passive"))
      (node (ref "U1") (pin "P$B3") (pinfunction "DCC_P$B3") (pintype "output"))
    )
    (net (code "44") (name "Net-(U1-DEC2)") (class "Default")
      (node (ref "C13") (pin "2") (pinfunction "2_2") (pintype "passive"))
      (node (ref "U1") (pin "P$A18") (pinfunction "DEC2_P$A18") (pintype "bidirectional"))
    )
    (net (code "45") (name "Net-(U1-DEC3V3)") (class "Default")
      (node (ref "C20\\") (pin "1") (pinfunction "1_1") (pintype "passive"))
      (node (ref "U1") (pin "P$AC5") (pinfunction "DEC3V3_P$AC5") (pintype "bidirectional"))
    )
    (net (code "46") (name "Net-(U1-DEC5)") (class "Default")
      (node (ref "C9") (pin "2") (pinfunction "2_2") (pintype "passive"))
      (node (ref "U1") (pin "P$N24") (pinfunction "DEC5_P$N24") (pintype "bidirectional"))
    )
    (net (code "47") (name "Net-(U1-XC1)") (class "Default")
      (node (ref "C1") (pin "2") (pinfunction "2_2") (pintype "passive"))
      (node (ref "U1") (pin "P$B24") (pinfunction "XC1_P$B24") (pintype "input"))
      (node (ref "X1") (pin "1") (pinfunction "1_1") (pintype "passive"))
    )
    (net (code "48") (name "Net-(U1-XC2)") (class "Default")
      (node (ref "C2") (pin "1") (pinfunction "1_1") (pintype "passive"))
      (node (ref "U1") (pin "P$A23") (pinfunction "XC2_P$A23") (pintype "output"))
      (node (ref "X1") (pin "3") (pinfunction "3_3") (pintype "passive"))
    )
    (net (code "49") (name "OUT+") (class "Default")
      (node (ref "IC2") (pin "A3") (pinfunction "OUT+_A3") (pintype "bidirectional"))
      (node (ref "TP_OP") (pin "TP") (pinfunction "TP_TP") (pintype "input"))
    )
    (net (code "50") (name "OUT-") (class "Default")
      (node (ref "IC2") (pin "C3") (pinfunction "OUT-_C3") (pintype "bidirectional"))
      (node (ref "TP_ON") (pin "TP") (pinfunction "TP_TP") (pintype "input"))
    )
    (net (code "51") (name "P0.00{slash}XL1") (class "Default")
      (node (ref "C17") (pin "2") (pinfunction "2_2") (pintype "passive"))
      (node (ref "U1") (pin "P$D2") (pinfunction "P0.00/XL1_P$D2") (pintype "bidirectional"))
      (node (ref "X2") (pin "1") (pinfunction "1_1") (pintype "passive"))
    )
    (net (code "52") (name "P0.01{slash}XL2") (class "Default")
      (node (ref "C18") (pin "2") (pinfunction "2_2") (pintype "passive"))
      (node (ref "U1") (pin "P$F2") (pinfunction "P0.01/XL2_P$F2") (pintype "bidirectional"))
      (node (ref "X2") (pin "2") (pinfunction "2_2") (pintype "passive"))
    )
    (net (code "53") (name "P0.13") (class "Default")
      (node (ref "C30") (pin "1") (pinfunction "1_1") (pintype "passive"))
      (node (ref "R5") (pin "1") (pinfunction "1_1") (pintype "bidirectional"))
      (node (ref "SW2") (pin "2") (pinfunction "2_2") (pintype "passive"))
      (node (ref "U1") (pin "P$AD8") (pinfunction "P0.13_P$AD8") (pintype "bidirectional"))
    )
    (net (code "54") (name "P0.14") (class "Default")
      (node (ref "C31") (pin "1") (pinfunction "1_1") (pintype "passive"))
      (node (ref "R8") (pin "1") (pinfunction "1_1") (pintype "bidirectional"))
      (node (ref "SW1") (pin "2") (pinfunction "2_2") (pintype "passive"))
      (node (ref "U1") (pin "P$AC9") (pinfunction "P0.14_P$AC9") (pintype "bidirectional"))
    )
    (net (code "55") (name "P1.01") (class "Default")
      (node (ref "Q1") (pin "1") (pinfunction "G_1") (pintype "bidirectional"))
      (node (ref "R_PWR_EDP") (pin "1") (pinfunction "1_1") (pintype "bidirectional"))
      (node (ref "U1") (pin "P$Y23") (pinfunction "P1.01_P$Y23") (pintype "bidirectional"))
    )
    (net (code "56") (name "P1.02") (class "Default")
      (node (ref "C29") (pin "1") (pinfunction "1_1") (pintype "passive"))
      (node (ref "R7") (pin "1") (pinfunction "1_1") (pintype "bidirectional"))
      (node (ref "SW3") (pin "2") (pinfunction "2_2") (pintype "passive"))
      (node (ref "U1") (pin "P$W24") (pinfunction "P1.02_P$W24") (pintype "bidirectional"))
    )
    (net (code "57") (name "PMIC_INT") (class "Default")
      (node (ref "IC1") (pin "A1") (pinfunction "~{INT}_A1") (pintype "bidirectional"))
      (node (ref "U1") (pin "P$T2") (pinfunction "P0.11_P$T2") (pintype "bidirectional"))
    )
    (net (code "58") (name "PREVGH") (class "Default")
      (node (ref "D5") (pin "1") (pinfunction "K_1") (pintype "bidirectional"))
      (node (ref "EPD_C9") (pin "2") (pinfunction "2_2") (pintype "passive"))
      (node (ref "J2") (pin "21") (pinfunction "21_21") (pintype "bidirectional"))
    )
    (net (code "59") (name "PREVGL") (class "Default")
      (node (ref "D2") (pin "2") (pinfunction "A_2") (pintype "bidirectional"))
      (node (ref "EPD_C11") (pin "2") (pinfunction "2_2") (pintype "passive"))
      (node (ref "J2") (pin "23") (pinfunction "23_23") (pintype "bidirectional"))
    )
    (net (code "60") (name "RESE") (class "Default")
      (node (ref "J2") (pin "3") (pinfunction "3_3") (pintype "bidirectional"))
      (node (ref "Q3") (pin "2") (pinfunction "S_2") (pintype "bidirectional"))
      (node (ref "R1_EP_DR") (pin "2") (pinfunction "2_2") (pintype "bidirectional"))
    )
    (net (code "61") (name "RESET") (class "Default")
      (node (ref "J1") (pin "6") (pinfunction "6_6") (pintype "bidirectional"))
      (node (ref "TP_RESET") (pin "TP") (pinfunction "TP_TP") (pintype "input"))
      (node (ref "U1") (pin "P$AC13") (pinfunction "P0.18/RESET_P$AC13") (pintype "bidirectional"))
    )
    (net (code "62") (name "SCK") (class "Default")
      (node (ref "J2") (pin "13") (pinfunction "13_13") (pintype "bidirectional"))
      (node (ref "U1") (pin "P$A12") (pinfunction "P0.02/AIN0_P$A12") (pintype "bidirectional"))
    )
    (net (code "63") (name "SCL") (class "Default")
      (node (ref "IC1") (pin "B1") (pinfunction "SCL_B1") (pintype "bidirectional"))
      (node (ref "IC2") (pin "C1") (pinfunction "SCL_C1") (pintype "bidirectional"))
      (node (ref "IC3") (pin "12") (pinfunction "SCX_12") (pintype "bidirectional"))
      (node (ref "R17") (pin "2") (pinfunction "2_2") (pintype "bidirectional"))
      (node (ref "R4") (pin "2") (pinfunction "2_2") (pintype "bidirectional"))
      (node (ref "TP_SCL") (pin "TP") (pinfunction "TP_TP") (pintype "input"))
      (node (ref "U1") (pin "P$M2") (pinfunction "P0.07_P$M2") (pintype "bidirectional"))
      (node (ref "U3") (pin "7") (pinfunction "SCL_7") (pintype "input"))
    )
    (net (code "64") (name "SDA") (class "Default")
      (node (ref "IC1") (pin "C1") (pinfunction "SDA_C1") (pintype "bidirectional"))
      (node (ref "IC2") (pin "B2") (pinfunction "SDA_B2") (pintype "bidirectional"))
      (node (ref "IC3") (pin "2") (pinfunction "SDX_2") (pintype "bidirectional"))
      (node (ref "R18") (pin "2") (pinfunction "2_2") (pintype "bidirectional"))
      (node (ref "R2") (pin "2") (pinfunction "2_2") (pintype "bidirectional"))
      (node (ref "TP_SDA") (pin "TP") (pinfunction "TP_TP") (pintype "input"))
      (node (ref "U1") (pin "P$L1") (pinfunction "P0.06_P$L1") (pintype "bidirectional"))
      (node (ref "U3") (pin "8") (pinfunction "SDA_8") (pintype "bidirectional"))
    )
    (net (code "65") (name "SWDCLK") (class "Default")
      (node (ref "J1") (pin "4") (pinfunction "4_4") (pintype "bidirectional"))
      (node (ref "TP_SWDCLK") (pin "TP") (pinfunction "TP_TP") (pintype "input"))
      (node (ref "U1") (pin "P$AA24") (pinfunction "SWDCLK_P$AA24") (pintype "input"))
    )
    (net (code "66") (name "SWDIO") (class "Default")
      (node (ref "J1") (pin "2") (pinfunction "2_2") (pintype "bidirectional"))
      (node (ref "TP_SWDIO") (pin "TP") (pinfunction "TP_TP") (pintype "input"))
      (node (ref "U1") (pin "P$AC24") (pinfunction "SWDIO_P$AC24") (pintype "bidirectional"))
    )
    (net (code "67") (name "SWO") (class "Default")
      (node (ref "TP_SWO") (pin "TP") (pinfunction "TP_TP") (pintype "input"))
      (node (ref "U1") (pin "P$AD22") (pinfunction "P1.00_P$AD22") (pintype "bidirectional"))
    )
    (net (code "68") (name "VBAT") (class "Default")
      (node (ref "C27") (pin "1") (pinfunction "1_1") (pintype "passive"))
      (node (ref "C37") (pin "1") (pinfunction "1_1") (pintype "passive"))
      (node (ref "IC1") (pin "C2") (pinfunction "BAT_C2") (pintype "bidirectional"))
      (node (ref "TP_VBAT") (pin "TP") (pinfunction "TP_TP") (pintype "input"))
      (node (ref "U3") (pin "2") (pinfunction "CELL_2") (pintype "power_in"))
      (node (ref "U3") (pin "3") (pinfunction "VDD_3") (pintype "power_in"))
    )
    (net (code "69") (name "VBUS") (class "Default")
      (node (ref "C21") (pin "1") (pinfunction "1_1") (pintype "passive"))
      (node (ref "C38") (pin "1") (pinfunction "1_1") (pintype "passive"))
      (node (ref "C42") (pin "1") (pinfunction "1_1") (pintype "passive"))
      (node (ref "C43") (pin "1") (pinfunction "1_1") (pintype "passive"))
      (node (ref "D1") (pin "5") (pinfunction "VBUS_5") (pintype "bidirectional"))
      (node (ref "IC1") (pin "A2") (pinfunction "IN_A2") (pintype "bidirectional"))
      (node (ref "J4") (pin "A4_B9") (pinfunction "VBUS_A4_B9") (pintype "power_in"))
      (node (ref "J4") (pin "A9_B4") (pinfunction "VBUS_A9_B4") (pintype "power_in"))
      (node (ref "U1") (pin "P$AD2") (pinfunction "VBUS_P$AD2") (pintype "power_in"))
    )
    (net (code "70") (name "VREG") (class "Default")
      (node (ref "C23") (pin "2") (pinfunction "2_2") (pintype "passive"))
      (node (ref "C24") (pin "2") (pinfunction "2_2") (pintype "passive"))
      (node (ref "C39") (pin "1") (pinfunction "1_1") (pintype "passive"))
      (node (ref "IC1") (pin "B2") (pinfunction "SYS_B2") (pintype "bidirectional"))
      (node (ref "IC9") (pin "A1") (pinfunction "EN_A1") (pintype "bidirectional"))
      (node (ref "IC9") (pin "A2") (pinfunction "VIN_1_A2") (pintype "bidirectional"))
      (node (ref "IC9") (pin "A3") (pinfunction "VIN_2_A3") (pintype "bidirectional"))
      (node (ref "TP_VREG") (pin "TP") (pinfunction "TP_TP") (pintype "input"))
    )
    (net (code "71") (name "unconnected-(ANT1-NC-Pad2)") (class "Default")
      (node (ref "ANT1") (pin "2") (pinfunction "NC_2") (pintype "no_connect"))
    )
    (net (code "72") (name "unconnected-(IC3-ASCL-Pad11)") (class "Default")
      (node (ref "IC3") (pin "11") (pinfunction "ASCL_11") (pintype "bidirectional"))
    )
    (net (code "73") (name "unconnected-(IC3-ASDA-Pad4)") (class "Default")
      (node (ref "IC3") (pin "4") (pinfunction "ASDA_4") (pintype "bidirectional"))
    )
    (net (code "74") (name "unconnected-(J2-Pad1)") (class "Default")
      (node (ref "J2") (pin "1") (pinfunction "1_1") (pintype "bidirectional"))
    )
    (net (code "75") (name "unconnected-(J2-Pad6)") (class "Default")
      (node (ref "J2") (pin "6") (pinfunction "6_6") (pintype "bidirectional"))
    )
    (net (code "76") (name "unconnected-(J2-Pad7)") (class "Default")
      (node (ref "J2") (pin "7") (pinfunction "7_7") (pintype "bidirectional"))
    )
    (net (code "77") (name "unconnected-(J4-SBU1-PadA8)") (class "Default")
      (node (ref "J4") (pin "A8") (pinfunction "SBU1_A8") (pintype "bidirectional"))
    )
    (net (code "78") (name "unconnected-(J4-SBU2-PadB8)") (class "Default")
      (node (ref "J4") (pin "B8") (pinfunction "SBU2_B8") (pintype "bidirectional"))
    )
    (net (code "79") (name "unconnected-(U1-DCCH-PadP$AB2)") (class "Default")
      (node (ref "U1") (pin "P$AB2") (pinfunction "DCCH_P$AB2") (pintype "bidirectional"))
    )
    (net (code "80") (name "unconnected-(U1-P0.04{slash}AIN2-PadP$J1)") (class "Default")
      (node (ref "U1") (pin "P$J1") (pinfunction "P0.04/AIN2_P$J1") (pintype "bidirectional"))
    )
    (net (code "81") (name "unconnected-(U1-P0.09{slash}NFC1-PadP$L24)") (class "Default")
      (node (ref "U1") (pin "P$L24") (pinfunction "P0.09/NFC1_P$L24") (pintype "bidirectional"))
    )
    (net (code "82") (name "unconnected-(U1-P0.19-PadP$AC15)") (class "Default")
      (node (ref "U1") (pin "P$AC15") (pinfunction "P0.19_P$AC15") (pintype "bidirectional"))
    )
    (net (code "83") (name "unconnected-(U1-P0.20-PadP$AD16)") (class "Default")
      (node (ref "U1") (pin "P$AD16") (pinfunction "P0.20_P$AD16") (pintype "bidirectional"))
    )
    (net (code "84") (name "unconnected-(U1-P0.21-PadP$AC17)") (class "Default")
      (node (ref "U1") (pin "P$AC17") (pinfunction "P0.21_P$AC17") (pintype "bidirectional"))
    )
    (net (code "85") (name "unconnected-(U1-P0.22-PadP$AD18)") (class "Default")
      (node (ref "U1") (pin "P$AD18") (pinfunction "P0.22_P$AD18") (pintype "bidirectional"))
    )
    (net (code "86") (name "unconnected-(U1-P0.23-PadP$AC19)") (class "Default")
      (node (ref "U1") (pin "P$AC19") (pinfunction "P0.23_P$AC19") (pintype "bidirectional"))
    )
    (net (code "87") (name "unconnected-(U1-P0.24-PadP$AD20)") (class "Default")
      (node (ref "U1") (pin "P$AD20") (pinfunction "P0.24_P$AD20") (pintype "bidirectional"))
    )
    (net (code "88") (name "unconnected-(U1-P0.25-PadP$AC21)") (class "Default")
      (node (ref "U1") (pin "P$AC21") (pinfunction "P0.25_P$AC21") (pintype "bidirectional"))
    )
    (net (code "89") (name "unconnected-(U1-P0.26-PadP$G1)") (class "Default")
      (node (ref "U1") (pin "P$G1") (pinfunction "P0.26_P$G1") (pintype "bidirectional"))
    )
    (net (code "90") (name "unconnected-(U1-P0.27-PadP$H2)") (class "Default")
      (node (ref "U1") (pin "P$H2") (pinfunction "P0.27_P$H2") (pintype "bidirectional"))
    )
    (net (code "91") (name "unconnected-(U1-P0.28{slash}AIN4-PadP$B11)") (class "Default")
      (node (ref "U1") (pin "P$B11") (pinfunction "P0.28/AIN4_P$B11") (pintype "bidirectional"))
    )
    (net (code "92") (name "unconnected-(U1-P0.29{slash}AIN5-PadP$A10)") (class "Default")
      (node (ref "U1") (pin "P$A10") (pinfunction "P0.29/AIN5_P$A10") (pintype "bidirectional"))
    )
    (net (code "93") (name "unconnected-(U1-P0.30{slash}AIN6-PadP$B9)") (class "Default")
      (node (ref "U1") (pin "P$B9") (pinfunction "P0.30/AIN6_P$B9") (pintype "bidirectional"))
    )
    (net (code "94") (name "unconnected-(U1-P0.31{slash}AIN7-PadP$A8)") (class "Default")
      (node (ref "U1") (pin "P$A8") (pinfunction "P0.31/AIN7_P$A8") (pintype "bidirectional"))
    )
    (net (code "95") (name "unconnected-(U1-P1.03-PadP$V23)") (class "Default")
      (node (ref "U1") (pin "P$V23") (pinfunction "P1.03_P$V23") (pintype "bidirectional"))
    )
    (net (code "96") (name "unconnected-(U1-P1.04-PadP$U24)") (class "Default")
      (node (ref "U1") (pin "P$U24") (pinfunction "P1.04_P$U24") (pintype "bidirectional"))
    )
    (net (code "97") (name "unconnected-(U1-P1.05-PadP$T23)") (class "Default")
      (node (ref "U1") (pin "P$T23") (pinfunction "P1.05_P$T23") (pintype "bidirectional"))
    )
    (net (code "98") (name "unconnected-(U1-P1.06-PadP$R24)") (class "Default")
      (node (ref "U1") (pin "P$R24") (pinfunction "P1.06_P$R24") (pintype "bidirectional"))
    )
    (net (code "99") (name "unconnected-(U1-P1.07-PadP$P23)") (class "Default")
      (node (ref "U1") (pin "P$P23") (pinfunction "P1.07_P$P23") (pintype "bidirectional"))
    )
    (net (code "100") (name "unconnected-(U1-P1.09-PadP$R1)") (class "Default")
      (node (ref "U1") (pin "P$R1") (pinfunction "P1.09_P$R1") (pintype "bidirectional"))
    )
    (net (code "101") (name "unconnected-(U1-P1.10-PadP$A20)") (class "Default")
      (node (ref "U1") (pin "P$A20") (pinfunction "P1.10_P$A20") (pintype "bidirectional"))
    )
    (net (code "102") (name "unconnected-(U1-P1.11-PadP$B19)") (class "Default")
      (node (ref "U1") (pin "P$B19") (pinfunction "P1.11_P$B19") (pintype "bidirectional"))
    )
    (net (code "103") (name "unconnected-(U1-P1.12-PadP$B17)") (class "Default")
      (node (ref "U1") (pin "P$B17") (pinfunction "P1.12_P$B17") (pintype "bidirectional"))
    )
    (net (code "104") (name "unconnected-(U1-P1.13-PadP$A16)") (class "Default")
      (node (ref "U1") (pin "P$A16") (pinfunction "P1.13_P$A16") (pintype "bidirectional"))
    )
    (net (code "105") (name "unconnected-(U1-P1.14-PadP$B15)") (class "Default")
      (node (ref "U1") (pin "P$B15") (pinfunction "P1.14_P$B15") (pintype "bidirectional"))
    )
    (net (code "106") (name "unconnected-(U1-P1.15-PadP$A14)") (class "Default")
      (node (ref "U1") (pin "P$A14") (pinfunction "P1.15_P$A14") (pintype "bidirectional"))
    )
  )
)
